# MCU.net
KiCad netlist of a schematic drawn in Altium Designer
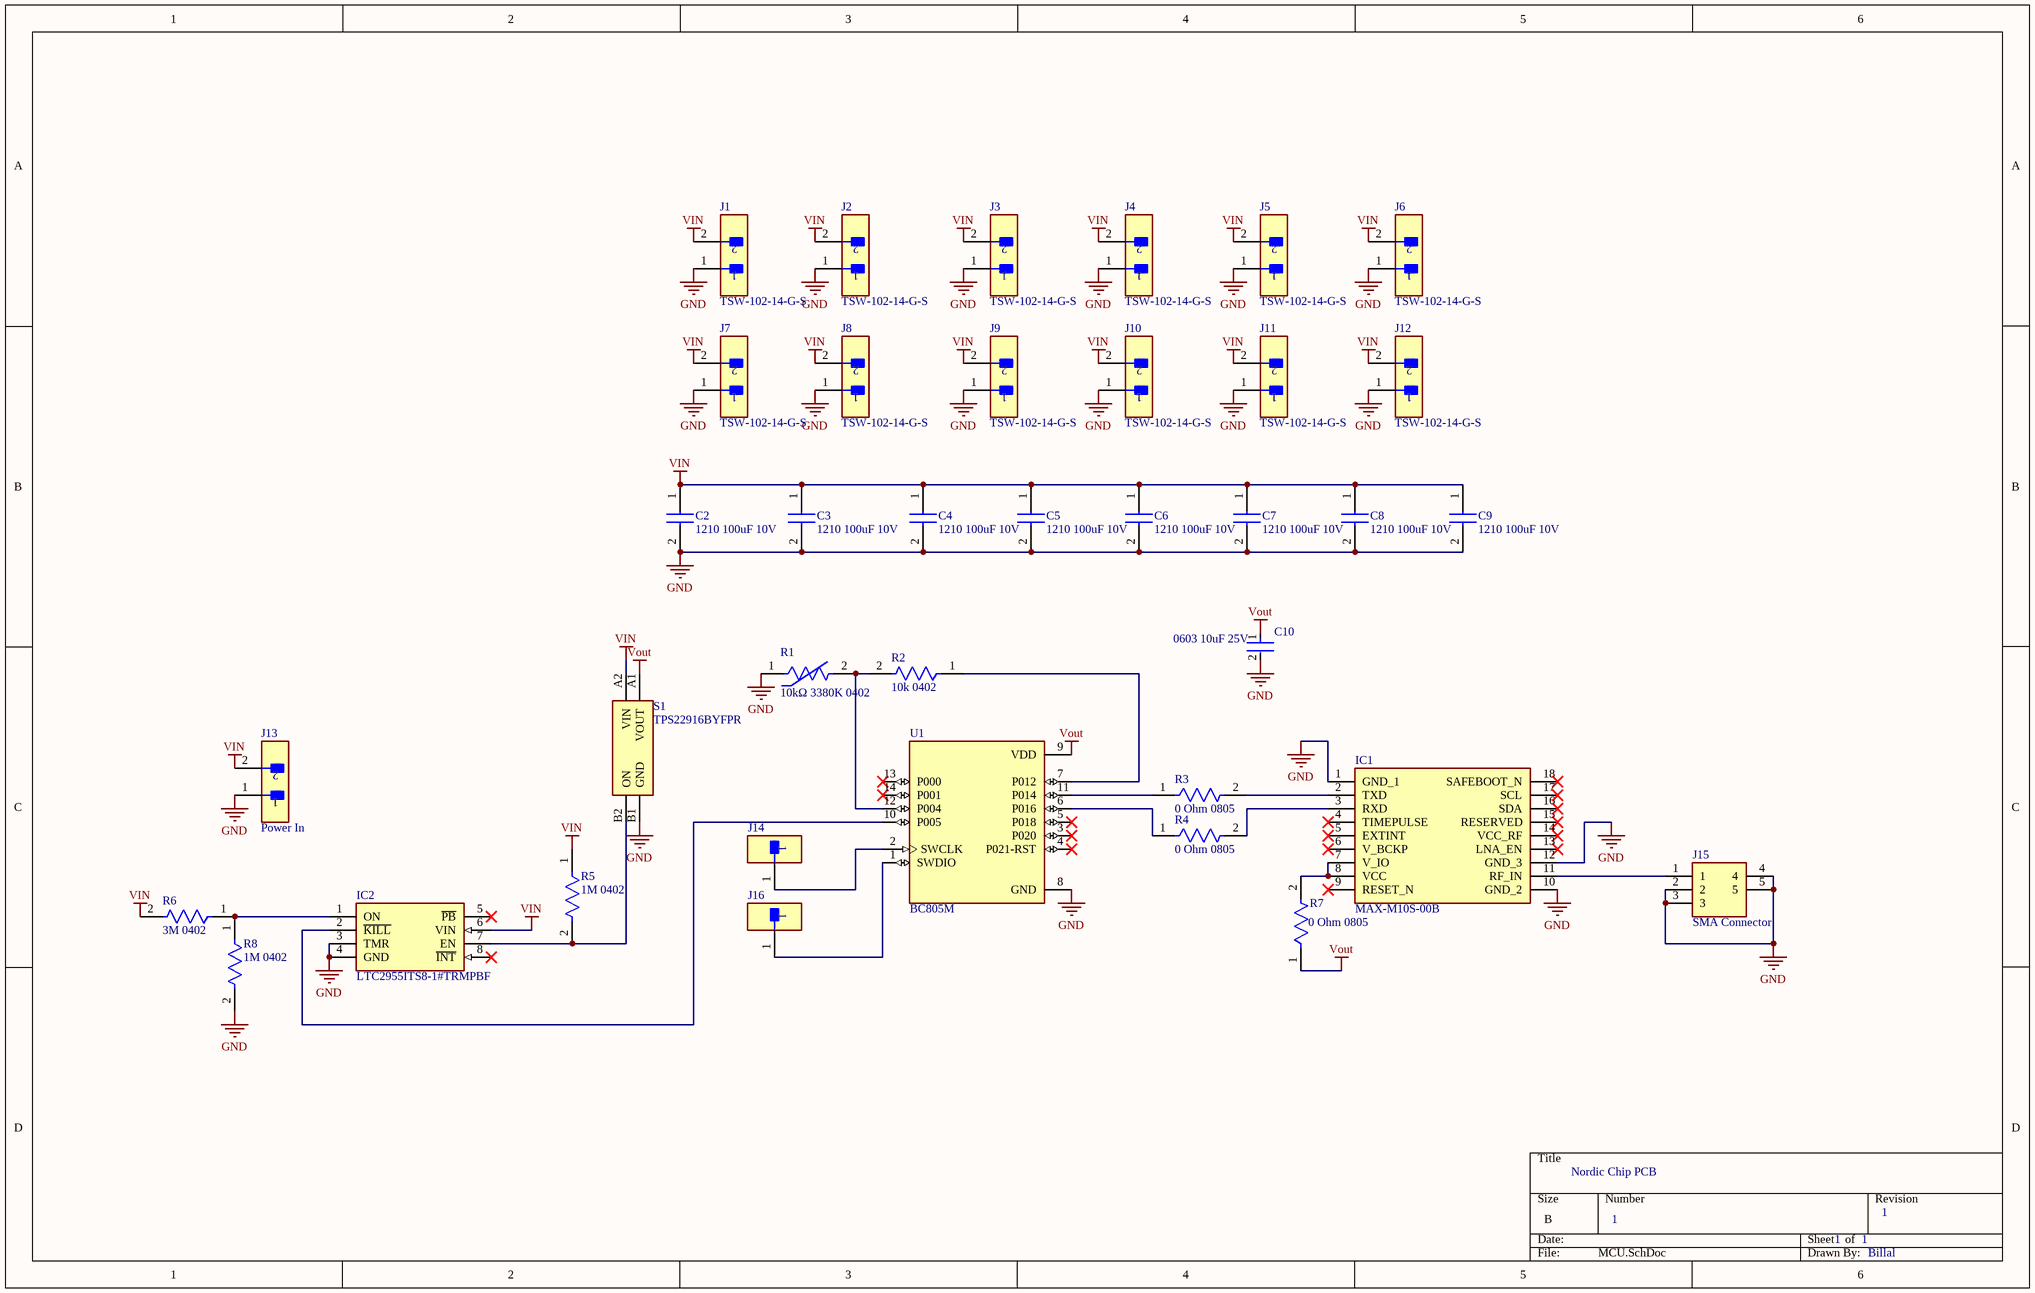
[diagram p0: MCU.SchDoc]

(export (version "E")
  (design (tool "Eeschema 10.0.6"))
  (components
    (comp (ref "C2")
      (value "1210 100uF 10V")
      (footprint "PcbLib2:CAPC3225X280N")
      (description "C23742")
      (fields
        (field (name "MANUFACTURER_PART_NUMBER") "CL32A107MPVNNNE")
        (field (name "MOUSER PART NUMBER") "187-CL32A107MPVNNNE")
      )
      (libsource (lib "*") (part "CL32A107MPVNNNE"))
    )
    (comp (ref "C3")
      (value "1210 100uF 10V")
      (footprint "PcbLib2:CAPC3225X280N")
      (description "C23742")
      (fields
        (field (name "MANUFACTURER_PART_NUMBER") "CL32A107MPVNNNE")
        (field (name "MOUSER PART NUMBER") "187-CL32A107MPVNNNE")
      )
      (libsource (lib "*") (part "CL32A107MPVNNNE"))
    )
    (comp (ref "C4")
      (value "1210 100uF 10V")
      (footprint "PcbLib2:CAPC3225X280N")
      (description "C23742")
      (fields
        (field (name "MANUFACTURER_PART_NUMBER") "CL32A107MPVNNNE")
        (field (name "MOUSER PART NUMBER") "187-CL32A107MPVNNNE")
      )
      (libsource (lib "*") (part "CL32A107MPVNNNE"))
    )
    (comp (ref "C5")
      (value "1210 100uF 10V")
      (footprint "PcbLib2:CAPC3225X280N")
      (description "C23742")
      (fields
        (field (name "MANUFACTURER_PART_NUMBER") "CL32A107MPVNNNE")
        (field (name "MOUSER PART NUMBER") "187-CL32A107MPVNNNE")
      )
      (libsource (lib "*") (part "CL32A107MPVNNNE"))
    )
    (comp (ref "C6")
      (value "1210 100uF 10V")
      (footprint "PcbLib2:CAPC3225X280N")
      (description "C23742")
      (fields
        (field (name "MANUFACTURER_PART_NUMBER") "CL32A107MPVNNNE")
        (field (name "MOUSER PART NUMBER") "187-CL32A107MPVNNNE")
      )
      (libsource (lib "*") (part "CL32A107MPVNNNE"))
    )
    (comp (ref "C7")
      (value "1210 100uF 10V")
      (footprint "PcbLib2:CAPC3225X280N")
      (description "C23742")
      (fields
        (field (name "MANUFACTURER_PART_NUMBER") "CL32A107MPVNNNE")
        (field (name "MOUSER PART NUMBER") "187-CL32A107MPVNNNE")
      )
      (libsource (lib "*") (part "CL32A107MPVNNNE"))
    )
    (comp (ref "C8")
      (value "1210 100uF 10V")
      (footprint "PcbLib2:CAPC3225X280N")
      (description "C23742")
      (fields
        (field (name "MANUFACTURER_PART_NUMBER") "CL32A107MPVNNNE")
        (field (name "MOUSER PART NUMBER") "187-CL32A107MPVNNNE")
      )
      (libsource (lib "*") (part "CL32A107MPVNNNE"))
    )
    (comp (ref "C9")
      (value "1210 100uF 10V")
      (footprint "PcbLib2:CAPC3225X280N")
      (description "C23742")
      (fields
        (field (name "MANUFACTURER_PART_NUMBER") "CL32A107MPVNNNE")
        (field (name "MOUSER PART NUMBER") "187-CL32A107MPVNNNE")
      )
      (libsource (lib "*") (part "CL32A107MPVNNNE"))
    )
    (comp (ref "C10")
      (value "0603 10uF 25V")
      (footprint "FP-CC0603-DC-MFG")
      (description "C96446")
      (fields (field (name "TOLERANCE") "10%"))
      (libsource (lib "Altium Content Vault") (part "b4654b650e69147ec39a6b967a45e02"))
    )
    (comp (ref "IC1")
      (value "MAX-M10S-00B")
      (footprint "PcbLib2:MAXM10S00B")
      (description "C4153167")
      (fields (field (name "MOUSER PART NUMBER") "377-MAX-M10S-00B"))
      (libsource (lib "*") (part "MAX-M10S-00B"))
    )
    (comp (ref "IC2")
      (value "LTC2955ITS8-1#TRMPBF")
      (footprint "PcbLib2:SOT65P280X100-8N")
      (description "C473668")
      (fields (field (name "MOUSER PART NUMBER") "584-C2955ITS8-1TMPF"))
      (libsource (lib "*") (part "LTC2955ITS8-1#TRMPBF"))
    )
    (comp (ref "J1")
      (value "TSW-102-14-G-S")
      (footprint "FP-TSW-102-14-G-S-MFG")
      (description "CONN HEADER VERT 2POS 2.54MM")
      (libsource (lib "Altium Content Vault") (part "88c1139f9d239099ffebecbe3f7647a"))
    )
    (comp (ref "J2")
      (value "TSW-102-14-G-S")
      (footprint "FP-TSW-102-14-G-S-MFG")
      (description "CONN HEADER VERT 2POS 2.54MM")
      (libsource (lib "Altium Content Vault") (part "88c1139f9d239099ffebecbe3f7647a"))
    )
    (comp (ref "J3")
      (value "TSW-102-14-G-S")
      (footprint "FP-TSW-102-14-G-S-MFG")
      (description "CONN HEADER VERT 2POS 2.54MM")
      (libsource (lib "Altium Content Vault") (part "88c1139f9d239099ffebecbe3f7647a"))
    )
    (comp (ref "J4")
      (value "TSW-102-14-G-S")
      (footprint "FP-TSW-102-14-G-S-MFG")
      (description "CONN HEADER VERT 2POS 2.54MM")
      (libsource (lib "Altium Content Vault") (part "88c1139f9d239099ffebecbe3f7647a"))
    )
    (comp (ref "J5")
      (value "TSW-102-14-G-S")
      (footprint "FP-TSW-102-14-G-S-MFG")
      (description "CONN HEADER VERT 2POS 2.54MM")
      (libsource (lib "Altium Content Vault") (part "88c1139f9d239099ffebecbe3f7647a"))
    )
    (comp (ref "J6")
      (value "TSW-102-14-G-S")
      (footprint "FP-TSW-102-14-G-S-MFG")
      (description "CONN HEADER VERT 2POS 2.54MM")
      (libsource (lib "Altium Content Vault") (part "88c1139f9d239099ffebecbe3f7647a"))
    )
    (comp (ref "J7")
      (value "TSW-102-14-G-S")
      (footprint "FP-TSW-102-14-G-S-MFG")
      (description "CONN HEADER VERT 2POS 2.54MM")
      (libsource (lib "Altium Content Vault") (part "88c1139f9d239099ffebecbe3f7647a"))
    )
    (comp (ref "J8")
      (value "TSW-102-14-G-S")
      (footprint "FP-TSW-102-14-G-S-MFG")
      (description "CONN HEADER VERT 2POS 2.54MM")
      (libsource (lib "Altium Content Vault") (part "88c1139f9d239099ffebecbe3f7647a"))
    )
    (comp (ref "J9")
      (value "TSW-102-14-G-S")
      (footprint "FP-TSW-102-14-G-S-MFG")
      (description "CONN HEADER VERT 2POS 2.54MM")
      (libsource (lib "Altium Content Vault") (part "88c1139f9d239099ffebecbe3f7647a"))
    )
    (comp (ref "J10")
      (value "TSW-102-14-G-S")
      (footprint "FP-TSW-102-14-G-S-MFG")
      (description "CONN HEADER VERT 2POS 2.54MM")
      (libsource (lib "Altium Content Vault") (part "88c1139f9d239099ffebecbe3f7647a"))
    )
    (comp (ref "J11")
      (value "TSW-102-14-G-S")
      (footprint "FP-TSW-102-14-G-S-MFG")
      (description "CONN HEADER VERT 2POS 2.54MM")
      (libsource (lib "Altium Content Vault") (part "88c1139f9d239099ffebecbe3f7647a"))
    )
    (comp (ref "J12")
      (value "TSW-102-14-G-S")
      (footprint "FP-TSW-102-14-G-S-MFG")
      (description "CONN HEADER VERT 2POS 2.54MM")
      (libsource (lib "Altium Content Vault") (part "88c1139f9d239099ffebecbe3f7647a"))
    )
    (comp (ref "J13")
      (value "Power In")
      (footprint "FP-TSW-102-14-G-S-MFG")
      (description "CONN HEADER VERT 2POS 2.54MM")
      (libsource (lib "Altium Content Vault") (part "88c1139f9d239099ffebecbe3f7647a"))
    )
    (comp (ref "J14")
      (value "SCL_USB_Power")
      (footprint "FP-TSW-101-07-L-S-MFG")
      (description "CONN HEADER VERT 1POS")
      (libsource (lib "Altium Content Vault") (part "dd45045ce8184df9e99e12baf3f412c"))
    )
    (comp (ref "J15")
      (value "SMA Connector")
      (footprint "PcbLib2:733910070")
      (description "C588470")
      (fields
        (field (name "MANUFACTURER_PART_NUMBER") "73391-0070")
        (field (name "MOUSER PART NUMBER") "538-73391-0070")
      )
      (libsource (lib "*") (part "73391-0070"))
    )
    (comp (ref "J16")
      (value "SCL_USB_Power")
      (footprint "FP-TSW-101-07-L-S-MFG")
      (description "CONN HEADER VERT 1POS")
      (libsource (lib "Altium Content Vault") (part "dd45045ce8184df9e99e12baf3f412c"))
    )
    (comp (ref "R1")
      (value "10kΩ 3380K 0402")
      (footprint "FP-NCP15-NCU15-0_05-IPC_A")
      (description "C178739")
      (libsource (lib "Altium Content Vault") (part "3b148a6ebabc5fb4d708a66c052d352"))
    )
    (comp (ref "R2")
      (value "10k 0402")
      (footprint "FP-RMCF0402-MFG")
      (description "C25744")
      (fields (field (name "TOLERANCE") "5%"))
      (libsource (lib "Altium Content Vault") (part "1029c3af85768c4190bb7ad29bc67b5"))
    )
    (comp (ref "R3")
      (value "0 Ohm 0805")
      (footprint "FP-HCJ0805-MFG")
      (description "C17477")
      (libsource (lib "Altium Content Vault") (part "1029c3af85768c4190bb7ad29bc67b5"))
    )
    (comp (ref "R4")
      (value "0 Ohm 0805")
      (footprint "FP-HCJ0805-MFG")
      (description "C17477")
      (libsource (lib "Altium Content Vault") (part "1029c3af85768c4190bb7ad29bc67b5"))
    )
    (comp (ref "R5")
      (value "1M 0402")
      (footprint "FP-RMCF0402-MFG")
      (description "C25744")
      (fields (field (name "TOLERANCE") "5%"))
      (libsource (lib "Altium Content Vault") (part "1029c3af85768c4190bb7ad29bc67b5"))
    )
    (comp (ref "R6")
      (value "3M 0402")
      (footprint "FP-RMCF0402-MFG")
      (description "C25744")
      (fields (field (name "TOLERANCE") "5%"))
      (libsource (lib "Altium Content Vault") (part "1029c3af85768c4190bb7ad29bc67b5"))
    )
    (comp (ref "R7")
      (value "0 Ohm 0805")
      (footprint "FP-HCJ0805-MFG")
      (description "C17477")
      (libsource (lib "Altium Content Vault") (part "1029c3af85768c4190bb7ad29bc67b5"))
    )
    (comp (ref "R8")
      (value "1M 0402")
      (footprint "FP-RMCF0402-MFG")
      (description "C25744")
      (fields (field (name "TOLERANCE") "5%"))
      (libsource (lib "Altium Content Vault") (part "1029c3af85768c4190bb7ad29bc67b5"))
    )
    (comp (ref "S1")
      (value "TPS22916BYFPR")
      (footprint "PcbLib2:BGA4C40P2X2_78X78X50")
      (description "Switch")
      (fields (field (name "MOUSER PART NUMBER") "595-TPS22916BYFPR"))
      (libsource (lib "*") (part "TPS22916BYFPR"))
    )
    (comp (ref "U1")
      (value "BC805M")
      (footprint "XCVR_BC805M")
      (description "Bluetooth Bluetooth v5.2 Transceiver Module 2.4GHz PCB Trace Surface Mount")
      (fields (field (name "MF") "Fanstel Corp."))
      (libsource (lib "Nordic PCBlib") (part "BC805M"))
    )
  )
  (nets
    (net (code "1") (name "GND") (class "Default")
      (node (ref "C10") (pin "2") (pinfunction "2_2") (pintype "passive"))
      (node (ref "C2") (pin "2") (pinfunction "2_2") (pintype "passive"))
      (node (ref "C3") (pin "2") (pinfunction "2_2") (pintype "passive"))
      (node (ref "C4") (pin "2") (pinfunction "2_2") (pintype "passive"))
      (node (ref "C5") (pin "2") (pinfunction "2_2") (pintype "passive"))
      (node (ref "C6") (pin "2") (pinfunction "2_2") (pintype "passive"))
      (node (ref "C7") (pin "2") (pinfunction "2_2") (pintype "passive"))
      (node (ref "C8") (pin "2") (pinfunction "2_2") (pintype "passive"))
      (node (ref "C9") (pin "2") (pinfunction "2_2") (pintype "passive"))
      (node (ref "IC1") (pin "1") (pinfunction "GND_1_1") (pintype "passive"))
      (node (ref "IC1") (pin "10") (pinfunction "GND_2_10") (pintype "passive"))
      (node (ref "IC1") (pin "12") (pinfunction "GND_3_12") (pintype "passive"))
      (node (ref "IC2") (pin "3") (pinfunction "TMR_3") (pintype "passive"))
      (node (ref "IC2") (pin "4") (pinfunction "GND_4") (pintype "power_in"))
      (node (ref "J1") (pin "1") (pinfunction "1_1") (pintype "passive"))
      (node (ref "J10") (pin "1") (pinfunction "1_1") (pintype "passive"))
      (node (ref "J11") (pin "1") (pinfunction "1_1") (pintype "passive"))
      (node (ref "J12") (pin "1") (pinfunction "1_1") (pintype "passive"))
      (node (ref "J13") (pin "1") (pinfunction "1_1") (pintype "passive"))
      (node (ref "J15") (pin "2") (pinfunction "2_2") (pintype "passive"))
      (node (ref "J15") (pin "3") (pinfunction "3_3") (pintype "passive"))
      (node (ref "J15") (pin "4") (pinfunction "4_4") (pintype "passive"))
      (node (ref "J15") (pin "5") (pinfunction "5_5") (pintype "passive"))
      (node (ref "J2") (pin "1") (pinfunction "1_1") (pintype "passive"))
      (node (ref "J3") (pin "1") (pinfunction "1_1") (pintype "passive"))
      (node (ref "J4") (pin "1") (pinfunction "1_1") (pintype "passive"))
      (node (ref "J5") (pin "1") (pinfunction "1_1") (pintype "passive"))
      (node (ref "J6") (pin "1") (pinfunction "1_1") (pintype "passive"))
      (node (ref "J7") (pin "1") (pinfunction "1_1") (pintype "passive"))
      (node (ref "J8") (pin "1") (pinfunction "1_1") (pintype "passive"))
      (node (ref "J9") (pin "1") (pinfunction "1_1") (pintype "passive"))
      (node (ref "R1") (pin "1") (pinfunction "1_1") (pintype "passive"))
      (node (ref "R8") (pin "2") (pinfunction "2_2") (pintype "passive"))
      (node (ref "S1") (pin "B1") (pinfunction "GND_B1") (pintype "passive"))
      (node (ref "U1") (pin "8") (pinfunction "GND_8") (pintype "power_in"))
    )
    (net (code "2") (name "Net-(IC1-RF_IN)") (class "Default")
      (node (ref "IC1") (pin "11") (pinfunction "RF_IN_11") (pintype "passive"))
      (node (ref "J15") (pin "1") (pinfunction "1_1") (pintype "passive"))
    )
    (net (code "3") (name "Net-(IC1-RXD)") (class "Default")
      (node (ref "IC1") (pin "3") (pinfunction "RXD_3") (pintype "passive"))
      (node (ref "R4") (pin "2") (pinfunction "2_2") (pintype "passive"))
    )
    (net (code "4") (name "Net-(IC1-TXD)") (class "Default")
      (node (ref "IC1") (pin "2") (pinfunction "TXD_2") (pintype "passive"))
      (node (ref "R3") (pin "2") (pinfunction "2_2") (pintype "passive"))
    )
    (net (code "5") (name "Net-(IC1-VCC)") (class "Default")
      (node (ref "IC1") (pin "7") (pinfunction "V_IO_7") (pintype "passive"))
      (node (ref "IC1") (pin "8") (pinfunction "VCC_8") (pintype "passive"))
      (node (ref "R7") (pin "2") (pinfunction "2_2") (pintype "passive"))
    )
    (net (code "6") (name "Net-(IC2-EN)") (class "Default")
      (node (ref "IC2") (pin "7") (pinfunction "EN_7") (pintype "passive"))
      (node (ref "R5") (pin "2") (pinfunction "2_2") (pintype "passive"))
      (node (ref "S1") (pin "B2") (pinfunction "ON_B2") (pintype "passive"))
    )
    (net (code "7") (name "Net-(IC2-ON)") (class "Default")
      (node (ref "IC2") (pin "1") (pinfunction "ON_1") (pintype "passive"))
      (node (ref "R6") (pin "1") (pinfunction "1_1") (pintype "passive"))
      (node (ref "R8") (pin "1") (pinfunction "1_1") (pintype "passive"))
    )
    (net (code "8") (name "Net-(IC2-~{KILL})") (class "Default")
      (node (ref "IC2") (pin "2") (pinfunction "~{KILL}_2") (pintype "passive"))
      (node (ref "U1") (pin "10") (pinfunction "P005_10") (pintype "bidirectional"))
    )
    (net (code "9") (name "Net-(U1-P004)") (class "Default")
      (node (ref "R1") (pin "2") (pinfunction "2_2") (pintype "passive"))
      (node (ref "R2") (pin "2") (pinfunction "2_2") (pintype "passive"))
      (node (ref "U1") (pin "12") (pinfunction "P004_12") (pintype "bidirectional"))
    )
    (net (code "10") (name "Net-(U1-P012)") (class "Default")
      (node (ref "R2") (pin "1") (pinfunction "1_1") (pintype "passive"))
      (node (ref "U1") (pin "7") (pinfunction "P012_7") (pintype "bidirectional"))
    )
    (net (code "11") (name "Net-(U1-P014)") (class "Default")
      (node (ref "R3") (pin "1") (pinfunction "1_1") (pintype "passive"))
      (node (ref "U1") (pin "11") (pinfunction "P014_11") (pintype "bidirectional"))
    )
    (net (code "12") (name "Net-(U1-P016)") (class "Default")
      (node (ref "R4") (pin "1") (pinfunction "1_1") (pintype "passive"))
      (node (ref "U1") (pin "6") (pinfunction "P016_6") (pintype "bidirectional"))
    )
    (net (code "13") (name "Net-(U1-SWCLK)") (class "Default")
      (node (ref "J14") (pin "1") (pinfunction "1_1") (pintype "passive"))
      (node (ref "U1") (pin "2") (pinfunction "SWCLK_2") (pintype "input"))
    )
    (net (code "14") (name "Net-(U1-SWDIO)") (class "Default")
      (node (ref "J16") (pin "1") (pinfunction "1_1") (pintype "passive"))
      (node (ref "U1") (pin "1") (pinfunction "SWDIO_1") (pintype "bidirectional"))
    )
    (net (code "15") (name "VIN") (class "Default")
      (node (ref "C2") (pin "1") (pinfunction "1_1") (pintype "passive"))
      (node (ref "C3") (pin "1") (pinfunction "1_1") (pintype "passive"))
      (node (ref "C4") (pin "1") (pinfunction "1_1") (pintype "passive"))
      (node (ref "C5") (pin "1") (pinfunction "1_1") (pintype "passive"))
      (node (ref "C6") (pin "1") (pinfunction "1_1") (pintype "passive"))
      (node (ref "C7") (pin "1") (pinfunction "1_1") (pintype "passive"))
      (node (ref "C8") (pin "1") (pinfunction "1_1") (pintype "passive"))
      (node (ref "C9") (pin "1") (pinfunction "1_1") (pintype "passive"))
      (node (ref "IC2") (pin "6") (pinfunction "VIN_6") (pintype "input"))
      (node (ref "J1") (pin "2") (pinfunction "2_2") (pintype "passive"))
      (node (ref "J10") (pin "2") (pinfunction "2_2") (pintype "passive"))
      (node (ref "J11") (pin "2") (pinfunction "2_2") (pintype "passive"))
      (node (ref "J12") (pin "2") (pinfunction "2_2") (pintype "passive"))
      (node (ref "J13") (pin "2") (pinfunction "2_2") (pintype "passive"))
      (node (ref "J2") (pin "2") (pinfunction "2_2") (pintype "passive"))
      (node (ref "J3") (pin "2") (pinfunction "2_2") (pintype "passive"))
      (node (ref "J4") (pin "2") (pinfunction "2_2") (pintype "passive"))
      (node (ref "J5") (pin "2") (pinfunction "2_2") (pintype "passive"))
      (node (ref "J6") (pin "2") (pinfunction "2_2") (pintype "passive"))
      (node (ref "J7") (pin "2") (pinfunction "2_2") (pintype "passive"))
      (node (ref "J8") (pin "2") (pinfunction "2_2") (pintype "passive"))
      (node (ref "J9") (pin "2") (pinfunction "2_2") (pintype "passive"))
      (node (ref "R5") (pin "1") (pinfunction "1_1") (pintype "passive"))
      (node (ref "R6") (pin "2") (pinfunction "2_2") (pintype "passive"))
      (node (ref "S1") (pin "A2") (pinfunction "VIN_A2") (pintype "passive"))
    )
    (net (code "16") (name "Vout") (class "Default")
      (node (ref "C10") (pin "1") (pinfunction "1_1") (pintype "passive"))
      (node (ref "R7") (pin "1") (pinfunction "1_1") (pintype "passive"))
      (node (ref "S1") (pin "A1") (pinfunction "VOUT_A1") (pintype "passive"))
      (node (ref "U1") (pin "9") (pinfunction "VDD_9") (pintype "power_in"))
    )
    (net (code "17") (name "unconnected-(IC1-EXTINT-Pad5)") (class "Default")
      (node (ref "IC1") (pin "5") (pinfunction "EXTINT_5") (pintype "passive+no_connect"))
    )
    (net (code "18") (name "unconnected-(IC1-LNA_EN-Pad13)") (class "Default")
      (node (ref "IC1") (pin "13") (pinfunction "LNA_EN_13") (pintype "passive+no_connect"))
    )
    (net (code "19") (name "unconnected-(IC1-RESERVED-Pad15)") (class "Default")
      (node (ref "IC1") (pin "15") (pinfunction "RESERVED_15") (pintype "passive+no_connect"))
    )
    (net (code "20") (name "unconnected-(IC1-RESET_N-Pad9)") (class "Default")
      (node (ref "IC1") (pin "9") (pinfunction "RESET_N_9") (pintype "passive+no_connect"))
    )
    (net (code "21") (name "unconnected-(IC1-SAFEBOOT_N-Pad18)") (class "Default")
      (node (ref "IC1") (pin "18") (pinfunction "SAFEBOOT_N_18") (pintype "passive+no_connect"))
    )
    (net (code "22") (name "unconnected-(IC1-SCL-Pad17)") (class "Default")
      (node (ref "IC1") (pin "17") (pinfunction "SCL_17") (pintype "passive+no_connect"))
    )
    (net (code "23") (name "unconnected-(IC1-SDA-Pad16)") (class "Default")
      (node (ref "IC1") (pin "16") (pinfunction "SDA_16") (pintype "passive+no_connect"))
    )
    (net (code "24") (name "unconnected-(IC1-TIMEPULSE-Pad4)") (class "Default")
      (node (ref "IC1") (pin "4") (pinfunction "TIMEPULSE_4") (pintype "passive+no_connect"))
    )
    (net (code "25") (name "unconnected-(IC1-VCC_RF-Pad14)") (class "Default")
      (node (ref "IC1") (pin "14") (pinfunction "VCC_RF_14") (pintype "passive+no_connect"))
    )
    (net (code "26") (name "unconnected-(IC1-V_BCKP-Pad6)") (class "Default")
      (node (ref "IC1") (pin "6") (pinfunction "V_BCKP_6") (pintype "passive+no_connect"))
    )
    (net (code "27") (name "unconnected-(IC2-~{INT}-Pad8)") (class "Default")
      (node (ref "IC2") (pin "8") (pinfunction "~{INT}_8") (pintype "input+no_connect"))
    )
    (net (code "28") (name "unconnected-(IC2-~{PB}-Pad5)") (class "Default")
      (node (ref "IC2") (pin "5") (pinfunction "~{PB}_5") (pintype "passive+no_connect"))
    )
    (net (code "29") (name "unconnected-(U1-P000-Pad13)") (class "Default")
      (node (ref "U1") (pin "13") (pinfunction "P000_13") (pintype "bidirectional+no_connect"))
    )
    (net (code "30") (name "unconnected-(U1-P001-Pad14)") (class "Default")
      (node (ref "U1") (pin "14") (pinfunction "P001_14") (pintype "bidirectional+no_connect"))
    )
    (net (code "31") (name "unconnected-(U1-P018-Pad5)") (class "Default")
      (node (ref "U1") (pin "5") (pinfunction "P018_5") (pintype "bidirectional+no_connect"))
    )
    (net (code "32") (name "unconnected-(U1-P020-Pad3)") (class "Default")
      (node (ref "U1") (pin "3") (pinfunction "P020_3") (pintype "bidirectional+no_connect"))
    )
    (net (code "33") (name "unconnected-(U1-P021-RST-Pad4)") (class "Default")
      (node (ref "U1") (pin "4") (pinfunction "P021-RST_4") (pintype "bidirectional+no_connect"))
    )
  )
)
